# Sheet2_Power_Supply.net
KiCad netlist of a schematic drawn in Altium Designer
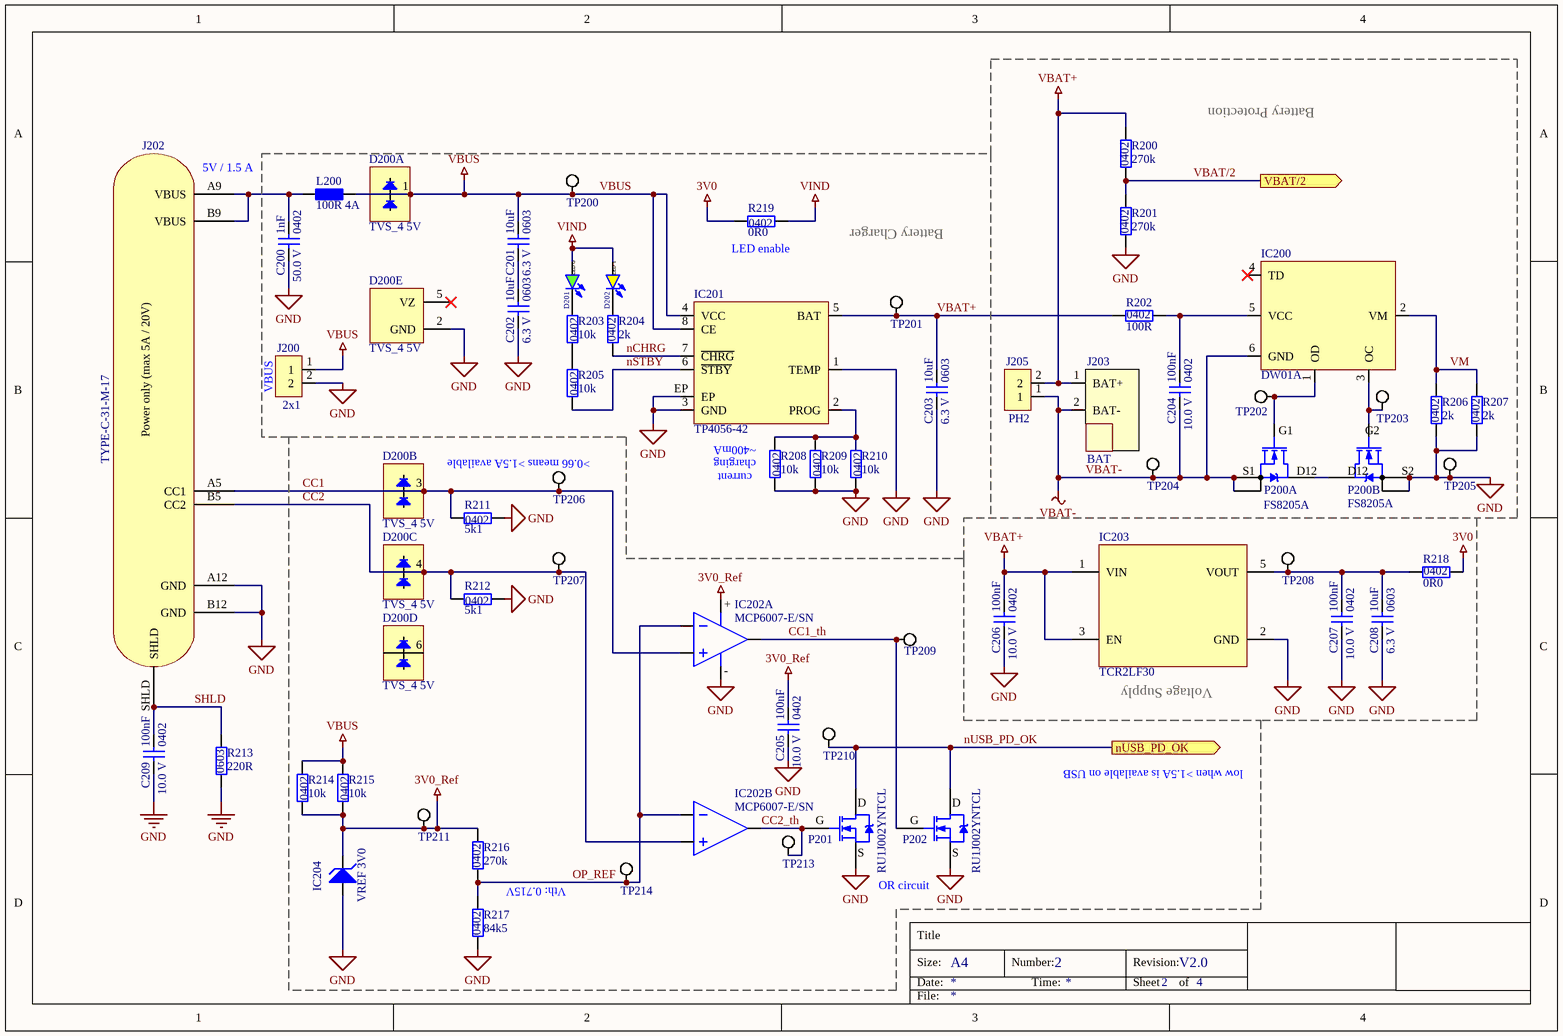
[diagram p0: Sheet2_Power_Supply.SchDoc]

(export (version "E")
  (design (tool "Eeschema 10.0.6"))
  (components
    (comp (ref "C200")
      (value "C 1nF 0402 50V")
      (footprint "0402")
      (description "CAP CER 1000PF 50V C0G/NP0 0402")
      (fields
        (field (name "MANUFACTURER") "Murata Electronics")
        (field (name "MANUFACTURER PART NUMBER") "GRM1555C1H102JA01J")
        (field (name "CAPACITANCE") "1nF")
        (field (name "VOLTAGE") "50.0 V")
      )
      (libsource (lib "CS_Part_Library") (part "CAP_1nF_50V_0402"))
    )
    (comp (ref "C201")
      (value "C 10uF 0603 6.3V")
      (footprint "0603")
      (description "CAP CER 10UF 6.3V X5R 0603")
      (fields
        (field (name "MANUFACTURER") "Taiyo Yuden")
        (field (name "MANUFACTURER PART NUMBER") "JMK107ABJ106MA-T")
        (field (name "CAPACITANCE") "10uF")
        (field (name "VOLTAGE") "6.3 V")
      )
      (libsource (lib "CS_Part_Library") (part "CAP_10uF_6V3_0603"))
    )
    (comp (ref "C202")
      (value "C 10uF 0603 6.3V")
      (footprint "0603")
      (description "CAP CER 10UF 6.3V X5R 0603")
      (fields
        (field (name "MANUFACTURER") "Taiyo Yuden")
        (field (name "MANUFACTURER PART NUMBER") "JMK107ABJ106MA-T")
        (field (name "CAPACITANCE") "10uF")
        (field (name "VOLTAGE") "6.3 V")
      )
      (libsource (lib "CS_Part_Library") (part "CAP_10uF_6V3_0603"))
    )
    (comp (ref "C203")
      (value "C 10uF 0603 6.3V")
      (footprint "0603")
      (description "CAP CER 10UF 6.3V X5R 0603")
      (fields
        (field (name "MANUFACTURER") "Taiyo Yuden")
        (field (name "MANUFACTURER PART NUMBER") "JMK107ABJ106MA-T")
        (field (name "CAPACITANCE") "10uF")
        (field (name "VOLTAGE") "6.3 V")
      )
      (libsource (lib "CS_Part_Library") (part "CAP_10uF_6V3_0603"))
    )
    (comp (ref "C204")
      (value "C 100nF 0402 10V")
      (footprint "0402")
      (description "CAP CER 0.1UF 10V X5R 0402")
      (fields
        (field (name "MANUFACTURER") "Samsung Electro-Mechanics")
        (field (name "MANUFACTURER PART NUMBER") "CL05A104MP5NNNC")
        (field (name "CAPACITANCE") "100nF")
        (field (name "VOLTAGE") "10.0 V")
      )
      (libsource (lib "CS_Part_Library") (part "CAP_100nF_10V_0402"))
    )
    (comp (ref "C205")
      (value "C 100nF 0402 10V")
      (footprint "0402")
      (description "CAP CER 0.1UF 10V X5R 0402")
      (fields
        (field (name "MANUFACTURER") "Samsung Electro-Mechanics")
        (field (name "MANUFACTURER PART NUMBER") "CL05A104MP5NNNC")
        (field (name "CAPACITANCE") "100nF")
        (field (name "VOLTAGE") "10.0 V")
      )
      (libsource (lib "CS_Part_Library") (part "CAP_100nF_10V_0402"))
    )
    (comp (ref "C206")
      (value "C 100nF 0402 10V")
      (footprint "0402")
      (description "CAP CER 0.1UF 10V X5R 0402")
      (fields
        (field (name "MANUFACTURER") "Samsung Electro-Mechanics")
        (field (name "MANUFACTURER PART NUMBER") "CL05A104MP5NNNC")
        (field (name "CAPACITANCE") "100nF")
        (field (name "VOLTAGE") "10.0 V")
      )
      (libsource (lib "CS_Part_Library") (part "CAP_100nF_10V_0402"))
    )
    (comp (ref "C207")
      (value "C 100nF 0402 10V")
      (footprint "0402")
      (description "CAP CER 0.1UF 10V X5R 0402")
      (fields
        (field (name "MANUFACTURER") "Samsung Electro-Mechanics")
        (field (name "MANUFACTURER PART NUMBER") "CL05A104MP5NNNC")
        (field (name "CAPACITANCE") "100nF")
        (field (name "VOLTAGE") "10.0 V")
      )
      (libsource (lib "CS_Part_Library") (part "CAP_100nF_10V_0402"))
    )
    (comp (ref "C208")
      (value "C 10uF 0603 6.3V")
      (footprint "0603")
      (description "CAP CER 10UF 6.3V X5R 0603")
      (fields
        (field (name "MANUFACTURER") "Taiyo Yuden")
        (field (name "MANUFACTURER PART NUMBER") "JMK107ABJ106MA-T")
        (field (name "CAPACITANCE") "10uF")
        (field (name "VOLTAGE") "6.3 V")
      )
      (libsource (lib "CS_Part_Library") (part "CAP_10uF_6V3_0603"))
    )
    (comp (ref "C209")
      (value "C 100nF 0402 10V")
      (footprint "0402")
      (description "CAP CER 0.1UF 10V X5R 0402")
      (fields
        (field (name "MANUFACTURER") "Samsung Electro-Mechanics")
        (field (name "MANUFACTURER PART NUMBER") "CL05A104MP5NNNC")
        (field (name "CAPACITANCE") "100nF")
        (field (name "VOLTAGE") "10.0 V")
      )
      (libsource (lib "CS_Part_Library") (part "CAP_100nF_10V_0402"))
    )
    (comp (ref "D200")
      (value "TVS_4 5V")
      (footprint "SOT-23-6")
      (description "TVS DIODE 5VWM 12.5VC SOT23-6")
      (fields
        (field (name "MANUFACTURER") "Comchip Technology")
        (field (name "MANUFACTURER PART NUMBER") "CPDT6-5V0UPC-HF")
      )
      (libsource (lib "CS_Part_Library") (part "D_TVS_U4_12V5"))
    )
    (comp (ref "D201")
      (value "LED G")
      (footprint "LED_0603")
      (description "LED GREEN DIFFUSED 0603 SMD")
      (fields
        (field (name "MANUFACTURER") "OSRAM Opto Semiconductors Inc.")
        (field (name "MANUFACTURER PART NUMBER") "LT Q39G-Q1OO-25-1")
      )
      (libsource (lib "CS_Part_Library") (part "D_LED_Green_0603"))
    )
    (comp (ref "D202")
      (value "LED Y")
      (footprint "LED_0603")
      (description "LED YELLOW DIFFUSED")
      (fields
        (field (name "MANUFACTURER") "Stanley Electric Co")
        (field (name "MANUFACTURER PART NUMBER") "FKY1111C-TR")
      )
      (libsource (lib "CS_Part_Library") (part "D_LED_Yellow_0603"))
    )
    (comp (ref "IC200")
      (value "DW01A")
      (footprint "SOT-23-6")
      (description "IC BATT MANAGEMENT SOT-23-6")
      (fields (field (name "MANUFACTURER") "PUOLOP"))
      (libsource (lib "Symbols") (part "IC_BAT_PROT_DW01A"))
    )
    (comp (ref "IC201")
      (value "TP4056-42")
      (footprint "SOIC-8-EP")
      (description "IC BATT CHG LI-ION 1CELL ESOP-8-EP")
      (fields
        (field (name "MANUFACTURER") "TOPPOWER(Nanjing Extension Microelectronics)")
        (field (name "MANUFACTURER PART NUMBER") "TP4056-42-ESOP8")
      )
      (libsource (lib "Symbols") (part "IC_BAT_CHGR_TP4056"))
    )
    (comp (ref "IC202")
      (value "MCP6007-E/SN")
      (footprint "SOIC-8")
      (description "DUAL, 1MHZ OP AMP, E TEMP")
      (fields (field (name "MANUFACTURER") "Microchip Technology"))
      (libsource (lib "CS_Part_Library") (part "IC_OpAmp_MCP6007-E/SN"))
    )
    (comp (ref "IC203")
      (value "TCR2LF30")
      (footprint "SOT-23-5")
      (description "IC REG LINEAR 3V 200MA SMV")
      (fields
        (field (name "MANUFACTURER") "Toshiba Semiconductor and Storage")
        (field (name "MANUFACTURER PART NUMBER") "TCR2LF30,LM(CT")
      )
      (libsource (lib "CS_Part_Library") (part "IC_Reg_TCR2LF30"))
    )
    (comp (ref "IC204")
      (value "VREF 3V0")
      (footprint "SOT-23-3")
      (description "IC VREF SHUNT 1% SOT23-3")
      (fields
        (field (name "MANUFACTURER") "Texas Instruments")
        (field (name "MANUFACTURER PART NUMBER") "LM4040DIM3X-3.0/NOPB")
      )
      (libsource (lib "Symbols") (part "IC_Ref_LM4040DIM3X-3.0"))
    )
    (comp (ref "J200")
      (value "2x1")
      (footprint "PH_1x2")
      (description "CONN HEADER VERT 2POS 2.54MM")
      (fields
        (field (name "MANUFACTURER") "Sullins Connector Solutions")
        (field (name "MANUFACTURER PART NUMBER") "PRPC002SAAN-RC")
      )
      (libsource (lib "CS_Part_Library") (part "J_MH2x1_2.54"))
    )
    (comp (ref "J202")
      (value "TYPE-C-31-M-17")
      (footprint "Con_TYPE-C-31-M-17")
      (description "USB4 GEN3, TYPE C, TOP MOUNT")
      (fields (field (name "MANUFACTURER") "Korean Hroparts Elec"))
      (libsource (lib "Symbols") (part "J_USB-C_2"))
    )
    (comp (ref "J203")
      (value "BAT")
      (footprint "J_BAT_CLIP_18650")
      (description "SMT Battery Connectors 18650")
      (fields (field (name "MANUFACTURER") "MYOUNG") (field (name "MANUFACTURER PART NUMBER") "MY-18650-02"))
      (libsource (lib "Symbols") (part "J_BAT_CLIP_18650_A"))
    )
    (comp (ref "J204")
      (value "BAT")
      (description "SMT Battery Connectors 18650")
      (fields (field (name "MANUFACTURER") "MYOUNG") (field (name "MANUFACTURER PART NUMBER") "MY-18650-02"))
      (libsource (lib "Symbols") (part "J_BAT_CLIP_18650_B"))
    )
    (comp (ref "J205")
      (value "PH2")
      (footprint "J_S2B-PH-K-S")
      (description "CONN HEADER R/A 2POS 2MM")
      (fields
        (field (name "MANUFACTURER") "JST Sales America Inc.")
        (field (name "MANUFACTURER PART NUMBER") "S2B-PH-KL(LF)(SN)")
      )
      (libsource (lib "Symbols") (part "J_S2B-PH-KL"))
    )
    (comp (ref "L200")
      (value "L Ferrite 100R 4A")
      (footprint "L_1206")
      (description "FIXED IND 100 4000MA 1206")
      (fields
        (field (name "MANUFACTURER") "Eaton - Electronics Division")
        (field (name "MANUFACTURER PART NUMBER") "MFBM1V3216-101-R")
        (field (name "INDUCTANCE") "100R 4A")
      )
      (libsource (lib "CS_Part_Library") (part "L_100R_4A"))
    )
    (comp (ref "P200")
      (value "P2 NMOS 20V 6A")
      (footprint "TSSOP-8_4.4mm")
      (description "MOSFET 2N_CH 20V 6A TSSOP-8")
      (fields
        (field (name "MANUFACTURER") "Fortune Semicon")
        (field (name "MANUFACTURER PART NUMBER") "FS8205A")
      )
      (libsource (lib "Symbols") (part "P_2NCH_20V_1W"))
    )
    (comp (ref "P201")
      (value "P_NCH_50V_150mW")
      (footprint "UMT3F")
      (description "MOSFET N-CH 50V 200MA UMT3F")
      (fields
        (field (name "MANUFACTURER") "Rohm Semiconductor")
        (field (name "MANUFACTURER PART NUMBER") "RU1J002YNTCL")
      )
      (libsource (lib "CS_Part_Library") (part "P_NCH_50V_150mW"))
    )
    (comp (ref "P202")
      (value "P_NCH_50V_150mW")
      (footprint "UMT3F")
      (description "MOSFET N-CH 50V 200MA UMT3F")
      (fields
        (field (name "MANUFACTURER") "Rohm Semiconductor")
        (field (name "MANUFACTURER PART NUMBER") "RU1J002YNTCL")
      )
      (libsource (lib "CS_Part_Library") (part "P_NCH_50V_150mW"))
    )
    (comp (ref "R200")
      (value "R 270k 0402")
      (footprint "0402")
      (description "RES 270K OHM 1% 1/16W 0402")
      (fields
        (field (name "MANUFACTURER") "YAGEO")
        (field (name "MANUFACTURER PART NUMBER") "RC0402FR-07270KL")
        (field (name "RESISTANCE") "270k")
      )
      (libsource (lib "CS_Part_Library") (part "R_270k_0402"))
    )
    (comp (ref "R201")
      (value "R 270k 0402")
      (footprint "0402")
      (description "RES 270K OHM 1% 1/16W 0402")
      (fields
        (field (name "MANUFACTURER") "YAGEO")
        (field (name "MANUFACTURER PART NUMBER") "RC0402FR-07270KL")
        (field (name "RESISTANCE") "270k")
      )
      (libsource (lib "CS_Part_Library") (part "R_270k_0402"))
    )
    (comp (ref "R202")
      (value "R 100R 0402")
      (footprint "0402")
      (description "RES 100 OHM 1% 1/16W 0402")
      (fields
        (field (name "MANUFACTURER") "Stackpole Electronics Inc")
        (field (name "MANUFACTURER PART NUMBER") "RMCF0402FT100R")
        (field (name "RESISTANCE") "100R")
      )
      (libsource (lib "CS_Part_Library") (part "R_100R_0402"))
    )
    (comp (ref "R203")
      (value "R 10k 0402")
      (footprint "0402")
      (description "RES 10K OHM 1% 1/16W 0402")
      (fields
        (field (name "MANUFACTURER") "YAGEO")
        (field (name "MANUFACTURER PART NUMBER") "RC0402FR-0710KL")
        (field (name "RESISTANCE") "10k")
      )
      (libsource (lib "CS_Part_Library") (part "R_10k_0402"))
    )
    (comp (ref "R204")
      (value "R 2k 0402")
      (footprint "0402")
      (description "RES 2K OHM 1% 1/16W 0402")
      (fields
        (field (name "MANUFACTURER") "Stackpole Electronics Inc")
        (field (name "MANUFACTURER PART NUMBER") "RMCF0402FT2K00")
        (field (name "RESISTANCE") "2k")
      )
      (libsource (lib "CS_Part_Library") (part "R_2k_0402"))
    )
    (comp (ref "R205")
      (value "R 10k 0402")
      (footprint "0402")
      (description "RES 10K OHM 1% 1/16W 0402")
      (fields
        (field (name "MANUFACTURER") "YAGEO")
        (field (name "MANUFACTURER PART NUMBER") "RC0402FR-0710KL")
        (field (name "RESISTANCE") "10k")
      )
      (libsource (lib "CS_Part_Library") (part "R_10k_0402"))
    )
    (comp (ref "R206")
      (value "R 2k 0402")
      (footprint "0402")
      (description "RES 2K OHM 1% 1/16W 0402")
      (fields
        (field (name "MANUFACTURER") "Stackpole Electronics Inc")
        (field (name "MANUFACTURER PART NUMBER") "RMCF0402FT2K00")
        (field (name "RESISTANCE") "2k")
      )
      (libsource (lib "CS_Part_Library") (part "R_2k_0402"))
    )
    (comp (ref "R207")
      (value "R 2k 0402")
      (footprint "0402")
      (description "RES 2K OHM 1% 1/16W 0402")
      (fields
        (field (name "MANUFACTURER") "Stackpole Electronics Inc")
        (field (name "MANUFACTURER PART NUMBER") "RMCF0402FT2K00")
        (field (name "RESISTANCE") "2k")
      )
      (libsource (lib "CS_Part_Library") (part "R_2k_0402"))
    )
    (comp (ref "R208")
      (value "R 10k 0402")
      (footprint "0402")
      (description "RES 10K OHM 1% 1/16W 0402")
      (fields
        (field (name "MANUFACTURER") "YAGEO")
        (field (name "MANUFACTURER PART NUMBER") "RC0402FR-0710KL")
        (field (name "RESISTANCE") "10k")
      )
      (libsource (lib "CS_Part_Library") (part "R_10k_0402"))
    )
    (comp (ref "R209")
      (value "R 10k 0402")
      (footprint "0402")
      (description "RES 10K OHM 1% 1/16W 0402")
      (fields
        (field (name "MANUFACTURER") "YAGEO")
        (field (name "MANUFACTURER PART NUMBER") "RC0402FR-0710KL")
        (field (name "RESISTANCE") "10k")
      )
      (libsource (lib "CS_Part_Library") (part "R_10k_0402"))
    )
    (comp (ref "R210")
      (value "R 10k 0402")
      (footprint "0402")
      (description "RES 10K OHM 1% 1/16W 0402")
      (fields
        (field (name "MANUFACTURER") "YAGEO")
        (field (name "MANUFACTURER PART NUMBER") "RC0402FR-0710KL")
        (field (name "RESISTANCE") "10k")
      )
      (libsource (lib "CS_Part_Library") (part "R_10k_0402"))
    )
    (comp (ref "R211")
      (value "R 5k1 0402")
      (footprint "0402")
      (description "RES 5.1K OHM 1% 1/16W 0402")
      (fields
        (field (name "MANUFACTURER") "Stackpole Electronics Inc")
        (field (name "MANUFACTURER PART NUMBER") "RMCF0402FT5K10")
        (field (name "RESISTANCE") "5k1")
      )
      (libsource (lib "CS_Part_Library") (part "R_5k1_0420"))
    )
    (comp (ref "R212")
      (value "R 5k1 0402")
      (footprint "0402")
      (description "RES 5.1K OHM 1% 1/16W 0402")
      (fields
        (field (name "MANUFACTURER") "Stackpole Electronics Inc")
        (field (name "MANUFACTURER PART NUMBER") "RMCF0402FT5K10")
        (field (name "RESISTANCE") "5k1")
      )
      (libsource (lib "CS_Part_Library") (part "R_5k1_0420"))
    )
    (comp (ref "R213")
      (value "R 220R 0603")
      (footprint "0603")
      (description "RES 220 OHM 1% 1/10W 0603")
      (fields
        (field (name "MANUFACTURER") "Stackpole Electronics Inc")
        (field (name "MANUFACTURER PART NUMBER") "RMCF0603FT220R")
        (field (name "RESISTANCE") "220R")
      )
      (libsource (lib "CS_Part_Library") (part "R_220R_0603"))
    )
    (comp (ref "R214")
      (value "R 10k 0402")
      (footprint "0402")
      (description "RES 10K OHM 1% 1/16W 0402")
      (fields
        (field (name "MANUFACTURER") "YAGEO")
        (field (name "MANUFACTURER PART NUMBER") "RC0402FR-0710KL")
        (field (name "RESISTANCE") "10k")
      )
      (libsource (lib "CS_Part_Library") (part "R_10k_0402"))
    )
    (comp (ref "R215")
      (value "R 10k 0402")
      (footprint "0402")
      (description "RES 10K OHM 1% 1/16W 0402")
      (fields
        (field (name "MANUFACTURER") "YAGEO")
        (field (name "MANUFACTURER PART NUMBER") "RC0402FR-0710KL")
        (field (name "RESISTANCE") "10k")
      )
      (libsource (lib "CS_Part_Library") (part "R_10k_0402"))
    )
    (comp (ref "R216")
      (value "R 270k 0402")
      (footprint "0402")
      (description "RES 270K OHM 1% 1/16W 0402")
      (fields
        (field (name "MANUFACTURER") "YAGEO")
        (field (name "MANUFACTURER PART NUMBER") "RC0402FR-07270KL")
        (field (name "RESISTANCE") "270k")
      )
      (libsource (lib "CS_Part_Library") (part "R_270k_0402"))
    )
    (comp (ref "R217")
      (value "R 84k5 0402")
      (footprint "0402")
      (description "RES SMD 84.5K OHM 1% 1/16W 0402")
      (fields
        (field (name "MANUFACTURER") "Vishay Dale")
        (field (name "MANUFACTURER PART NUMBER") "CRCW040284K5FKED")
        (field (name "RESISTANCE") "84k5")
      )
      (libsource (lib "CS_Part_Library") (part "R_84k5_0402"))
    )
    (comp (ref "R218")
      (value "R 0R0 0402")
      (footprint "0402")
      (description "RES 0 OHM JUMPER 1/16W 0402")
      (fields
        (field (name "MANUFACTURER") "Stackpole Electronics Inc")
        (field (name "MANUFACTURER PART NUMBER") "RMCF0402ZT0R00")
        (field (name "RESISTANCE") "0R0")
      )
      (libsource (lib "") (part "R_0R0_0402_1"))
    )
    (comp (ref "R219")
      (value "R 0R0 0402")
      (footprint "0402")
      (description "RES 0 OHM JUMPER 1/16W 0402")
      (fields
        (field (name "MANUFACTURER") "Stackpole Electronics Inc")
        (field (name "MANUFACTURER PART NUMBER") "RMCF0402ZT0R00")
        (field (name "RESISTANCE") "0R0")
      )
      (libsource (lib "CS_Part_Library") (part "R_0R0_0402"))
    )
    (comp (ref "TP200")
      (value "TP")
      (footprint "TP_1mm")
      (description "Test Point 1mm")
      (libsource (lib "CS_Part_Library") (part "TP_1mm"))
    )
    (comp (ref "TP201")
      (value "TP")
      (footprint "TP_1mm")
      (description "Test Point 1mm")
      (libsource (lib "CS_Part_Library") (part "TP_1mm"))
    )
    (comp (ref "TP202")
      (value "TP")
      (footprint "TP_1mm")
      (description "Test Point 1mm")
      (libsource (lib "CS_Part_Library") (part "TP_1mm"))
    )
    (comp (ref "TP203")
      (value "TP")
      (footprint "TP_1mm")
      (description "Test Point 1mm")
      (libsource (lib "CS_Part_Library") (part "TP_1mm"))
    )
    (comp (ref "TP204")
      (value "TP")
      (footprint "TP_1mm")
      (description "Test Point 1mm")
      (libsource (lib "CS_Part_Library") (part "TP_1mm"))
    )
    (comp (ref "TP205")
      (value "TP")
      (footprint "TP_1mm")
      (description "Test Point 1mm")
      (libsource (lib "CS_Part_Library") (part "TP_1mm"))
    )
    (comp (ref "TP206")
      (value "TP")
      (footprint "TP_1mm")
      (description "Test Point 1mm")
      (libsource (lib "CS_Part_Library") (part "TP_1mm"))
    )
    (comp (ref "TP207")
      (value "TP")
      (footprint "TP_1mm")
      (description "Test Point 1mm")
      (libsource (lib "CS_Part_Library") (part "TP_1mm"))
    )
    (comp (ref "TP208")
      (value "TP")
      (footprint "TP_1mm")
      (description "Test Point 1mm")
      (libsource (lib "CS_Part_Library") (part "TP_1mm"))
    )
    (comp (ref "TP209")
      (value "TP")
      (footprint "TP_1mm")
      (description "Test Point 1mm")
      (libsource (lib "CS_Part_Library") (part "TP_1mm"))
    )
    (comp (ref "TP210")
      (value "TP")
      (footprint "TP_1mm")
      (description "Test Point 1mm")
      (libsource (lib "CS_Part_Library") (part "TP_1mm"))
    )
    (comp (ref "TP211")
      (value "TP")
      (footprint "TP_1mm")
      (description "Test Point 1mm")
      (libsource (lib "CS_Part_Library") (part "TP_1mm"))
    )
    (comp (ref "TP213")
      (value "TP")
      (footprint "TP_1mm")
      (description "Test Point 1mm")
      (libsource (lib "CS_Part_Library") (part "TP_1mm"))
    )
    (comp (ref "TP214")
      (value "TP")
      (footprint "TP_1mm")
      (description "Test Point 1mm")
      (libsource (lib "CS_Part_Library") (part "TP_1mm"))
    )
  )
  (nets
    (net (code "1") (name "/CC1") (class "Default")
      (node (ref "D200") (pin "3") (pinfunction "3_3") (pintype "passive"))
      (node (ref "IC202") (pin "3") (pinfunction "INA+_3") (pintype "passive"))
      (node (ref "J202") (pin "A5") (pinfunction "CC1_A5") (pintype "passive"))
      (node (ref "R211") (pin "2") (pinfunction "2_2") (pintype "passive"))
      (node (ref "TP206") (pin "1") (pinfunction "TP_1") (pintype "passive"))
    )
    (net (code "2") (name "/CC1_th") (class "Default")
      (node (ref "IC202") (pin "1") (pinfunction "OUTA_1") (pintype "passive"))
      (node (ref "P202") (pin "1") (pinfunction "G_1") (pintype "passive"))
      (node (ref "TP209") (pin "1") (pinfunction "TP_1") (pintype "passive"))
    )
    (net (code "3") (name "/CC2") (class "Default")
      (node (ref "D200") (pin "4") (pinfunction "4_4") (pintype "passive"))
      (node (ref "IC202") (pin "5") (pinfunction "INB+_5") (pintype "passive"))
      (node (ref "J202") (pin "B5") (pinfunction "CC2_B5") (pintype "passive"))
      (node (ref "R212") (pin "2") (pinfunction "2_2") (pintype "passive"))
      (node (ref "TP207") (pin "1") (pinfunction "TP_1") (pintype "passive"))
    )
    (net (code "4") (name "/CC2_th") (class "Default")
      (node (ref "IC202") (pin "7") (pinfunction "OUTB_7") (pintype "passive"))
      (node (ref "P201") (pin "1") (pinfunction "G_1") (pintype "passive"))
      (node (ref "TP213") (pin "1") (pinfunction "TP_1") (pintype "passive"))
    )
    (net (code "5") (name "/OP_REF") (class "Default")
      (node (ref "IC202") (pin "2") (pinfunction "INA-_2") (pintype "passive"))
      (node (ref "IC202") (pin "6") (pinfunction "INB-_6") (pintype "passive"))
      (node (ref "R216") (pin "1") (pinfunction "1_1") (pintype "passive"))
      (node (ref "R217") (pin "2") (pinfunction "2_2") (pintype "passive"))
      (node (ref "TP214") (pin "1") (pinfunction "TP_1") (pintype "passive"))
    )
    (net (code "6") (name "/SHLD") (class "Default")
      (node (ref "C209") (pin "2") (pinfunction "2_2") (pintype "passive"))
      (node (ref "J202") (pin "SHLD") (pinfunction "SHLD_SHLD") (pintype "passive"))
      (node (ref "R213") (pin "2") (pinfunction "2_2") (pintype "passive"))
    )
    (net (code "7") (name "/VBAT{slash}2") (class "Default")
      (node (ref "R200") (pin "1") (pinfunction "1_1") (pintype "passive"))
      (node (ref "R201") (pin "2") (pinfunction "2_2") (pintype "passive"))
    )
    (net (code "8") (name "/VM") (class "Default")
      (node (ref "IC200") (pin "2") (pinfunction "VM_2") (pintype "passive"))
      (node (ref "R206") (pin "2") (pinfunction "2_2") (pintype "passive"))
      (node (ref "R207") (pin "2") (pinfunction "2_2") (pintype "passive"))
    )
    (net (code "9") (name "/nCHRG") (class "Default")
      (node (ref "IC201") (pin "7") (pinfunction "~{CHRG}_7") (pintype "passive"))
      (node (ref "R204") (pin "1") (pinfunction "1_1") (pintype "passive"))
    )
    (net (code "10") (name "/nSTBY") (class "Default")
      (node (ref "IC201") (pin "6") (pinfunction "~{STBY}_6") (pintype "passive"))
      (node (ref "R205") (pin "1") (pinfunction "1_1") (pintype "passive"))
    )
    (net (code "11") (name "/nUSB_PD_OK") (class "Default")
      (node (ref "P201") (pin "3") (pinfunction "D_3") (pintype "passive"))
      (node (ref "P202") (pin "3") (pinfunction "D_3") (pintype "passive"))
      (node (ref "TP210") (pin "1") (pinfunction "TP_1") (pintype "passive"))
    )
    (net (code "12") (name "3V0") (class "Default")
      (node (ref "R218") (pin "2") (pinfunction "2_2") (pintype "passive"))
      (node (ref "R219") (pin "2") (pinfunction "2_2") (pintype "passive"))
    )
    (net (code "13") (name "3V0_Ref") (class "Default")
      (node (ref "C205") (pin "2") (pinfunction "2_2") (pintype "passive"))
      (node (ref "IC202") (pin "8") (pinfunction "VDD_8") (pintype "passive"))
      (node (ref "IC204") (pin "1") (pinfunction "K_1") (pintype "passive"))
      (node (ref "R214") (pin "1") (pinfunction "1_1") (pintype "passive"))
      (node (ref "R215") (pin "1") (pinfunction "1_1") (pintype "passive"))
      (node (ref "R216") (pin "2") (pinfunction "2_2") (pintype "passive"))
      (node (ref "TP211") (pin "1") (pinfunction "TP_1") (pintype "passive"))
    )
    (net (code "14") (name "GND") (class "Default")
      (node (ref "C200") (pin "1") (pinfunction "1_1") (pintype "passive"))
      (node (ref "C202") (pin "1") (pinfunction "1_1") (pintype "passive"))
      (node (ref "C203") (pin "1") (pinfunction "1_1") (pintype "passive"))
      (node (ref "C205") (pin "1") (pinfunction "1_1") (pintype "passive"))
      (node (ref "C206") (pin "1") (pinfunction "1_1") (pintype "passive"))
      (node (ref "C207") (pin "1") (pinfunction "1_1") (pintype "passive"))
      (node (ref "C208") (pin "1") (pinfunction "1_1") (pintype "passive"))
      (node (ref "C209") (pin "1") (pinfunction "1_1") (pintype "passive"))
      (node (ref "D200") (pin "2") (pinfunction "GND_2") (pintype "passive"))
      (node (ref "IC201") (pin "1") (pinfunction "TEMP_1") (pintype "passive"))
      (node (ref "IC201") (pin "3") (pinfunction "GND_3") (pintype "passive"))
      (node (ref "IC201") (pin "EP") (pinfunction "EP_EP") (pintype "passive"))
      (node (ref "IC202") (pin "4") (pinfunction "VSS_4") (pintype "passive"))
      (node (ref "IC203") (pin "2") (pinfunction "GND_2") (pintype "passive"))
      (node (ref "IC204") (pin "2") (pinfunction "A_2") (pintype "passive"))
      (node (ref "J200") (pin "2") (pinfunction "2_2") (pintype "passive"))
      (node (ref "J202") (pin "A12") (pinfunction "GND_A12") (pintype "passive"))
      (node (ref "J202") (pin "B12") (pinfunction "GND_B12") (pintype "passive"))
      (node (ref "P200") (pin "6") (pinfunction "S2_6") (pintype "passive"))
      (node (ref "P200") (pin "7") (pinfunction "S2_7") (pintype "passive"))
      (node (ref "P201") (pin "2") (pinfunction "S_2") (pintype "passive"))
      (node (ref "P202") (pin "2") (pinfunction "S_2") (pintype "passive"))
      (node (ref "R201") (pin "1") (pinfunction "1_1") (pintype "passive"))
      (node (ref "R206") (pin "1") (pinfunction "1_1") (pintype "passive"))
      (node (ref "R207") (pin "1") (pinfunction "1_1") (pintype "passive"))
      (node (ref "R208") (pin "1") (pinfunction "1_1") (pintype "passive"))
      (node (ref "R209") (pin "1") (pinfunction "1_1") (pintype "passive"))
      (node (ref "R210") (pin "1") (pinfunction "1_1") (pintype "passive"))
      (node (ref "R211") (pin "1") (pinfunction "1_1") (pintype "passive"))
      (node (ref "R212") (pin "1") (pinfunction "1_1") (pintype "passive"))
      (node (ref "R213") (pin "1") (pinfunction "1_1") (pintype "passive"))
      (node (ref "R217") (pin "1") (pinfunction "1_1") (pintype "passive"))
      (node (ref "TP205") (pin "1") (pinfunction "TP_1") (pintype "passive"))
    )
    (net (code "15") (name "Net-(C200-Pad2)") (class "Default")
      (node (ref "C200") (pin "2") (pinfunction "2_2") (pintype "passive"))
      (node (ref "J202") (pin "A9") (pinfunction "VBUS_A9") (pintype "passive"))
      (node (ref "J202") (pin "B9") (pinfunction "VBUS_B9") (pintype "passive"))
      (node (ref "L200") (pin "1") (pinfunction "1_1") (pintype "passive"))
    )
    (net (code "16") (name "Net-(C201-Pad1)") (class "Default")
      (node (ref "C201") (pin "1") (pinfunction "1_1") (pintype "passive"))
      (node (ref "C202") (pin "2") (pinfunction "2_2") (pintype "passive"))
    )
    (net (code "17") (name "Net-(D201-PadK)") (class "Default")
      (node (ref "D201") (pin "K") (pinfunction "K_K") (pintype "passive"))
      (node (ref "R203") (pin "2") (pinfunction "2_2") (pintype "passive"))
    )
    (net (code "18") (name "Net-(D202-PadK)") (class "Default")
      (node (ref "D202") (pin "K") (pinfunction "K_K") (pintype "passive"))
      (node (ref "R204") (pin "2") (pinfunction "2_2") (pintype "passive"))
    )
    (net (code "19") (name "Net-(IC200-OC)") (class "Default")
      (node (ref "IC200") (pin "3") (pinfunction "OC_3") (pintype "passive"))
      (node (ref "P200") (pin "5") (pinfunction "G1_5") (pintype "passive"))
      (node (ref "TP203") (pin "1") (pinfunction "TP_1") (pintype "passive"))
    )
    (net (code "20") (name "Net-(IC200-OD)") (class "Default")
      (node (ref "IC200") (pin "1") (pinfunction "OD_1") (pintype "passive"))
      (node (ref "P200") (pin "4") (pinfunction "G1_4") (pintype "passive"))
      (node (ref "TP202") (pin "1") (pinfunction "TP_1") (pintype "passive"))
    )
    (net (code "21") (name "Net-(IC200-VCC)") (class "Default")
      (node (ref "C204") (pin "2") (pinfunction "2_2") (pintype "passive"))
      (node (ref "IC200") (pin "5") (pinfunction "VCC_5") (pintype "passive"))
      (node (ref "R202") (pin "2") (pinfunction "2_2") (pintype "passive"))
    )
    (net (code "22") (name "Net-(IC201-PROG)") (class "Default")
      (node (ref "IC201") (pin "2") (pinfunction "PROG_2") (pintype "passive"))
      (node (ref "R208") (pin "2") (pinfunction "2_2") (pintype "passive"))
      (node (ref "R209") (pin "2") (pinfunction "2_2") (pintype "passive"))
      (node (ref "R210") (pin "2") (pinfunction "2_2") (pintype "passive"))
    )
    (net (code "23") (name "Net-(IC203-VOUT)") (class "Default")
      (node (ref "C207") (pin "2") (pinfunction "2_2") (pintype "passive"))
      (node (ref "C208") (pin "2") (pinfunction "2_2") (pintype "passive"))
      (node (ref "IC203") (pin "5") (pinfunction "VOUT_5") (pintype "passive"))
      (node (ref "R218") (pin "1") (pinfunction "1_1") (pintype "passive"))
      (node (ref "TP208") (pin "1") (pinfunction "TP_1") (pintype "passive"))
    )
    (net (code "24") (name "Net-(P200A-D12)") (class "Default")
      (node (ref "P200") (pin "1") (pinfunction "D12_1") (pintype "passive"))
      (node (ref "P200") (pin "8") (pinfunction "D12_8") (pintype "passive"))
    )
    (net (code "25") (name "Net-(R203-Pad1)") (class "Default")
      (node (ref "R203") (pin "1") (pinfunction "1_1") (pintype "passive"))
      (node (ref "R205") (pin "2") (pinfunction "2_2") (pintype "passive"))
    )
    (net (code "26") (name "VBAT+") (class "Default")
      (node (ref "C203") (pin "2") (pinfunction "2_2") (pintype "passive"))
      (node (ref "C206") (pin "2") (pinfunction "2_2") (pintype "passive"))
      (node (ref "IC201") (pin "5") (pinfunction "BAT_5") (pintype "passive"))
      (node (ref "IC203") (pin "1") (pinfunction "VIN_1") (pintype "passive"))
      (node (ref "IC203") (pin "3") (pinfunction "EN_3") (pintype "passive"))
      (node (ref "J203") (pin "1") (pinfunction "BAT+_1") (pintype "passive"))
      (node (ref "J205") (pin "2") (pinfunction "2_2") (pintype "passive"))
      (node (ref "R200") (pin "2") (pinfunction "2_2") (pintype "passive"))
      (node (ref "R202") (pin "1") (pinfunction "1_1") (pintype "passive"))
      (node (ref "TP201") (pin "1") (pinfunction "TP_1") (pintype "passive"))
    )
    (net (code "27") (name "VBAT-") (class "Default")
      (node (ref "C204") (pin "1") (pinfunction "1_1") (pintype "passive"))
      (node (ref "IC200") (pin "6") (pinfunction "GND_6") (pintype "passive"))
      (node (ref "J203") (pin "2") (pinfunction "BAT-_2") (pintype "passive"))
      (node (ref "J205") (pin "1") (pinfunction "1_1") (pintype "passive"))
      (node (ref "P200") (pin "2") (pinfunction "S1_2") (pintype "passive"))
      (node (ref "P200") (pin "3") (pinfunction "S1_3") (pintype "passive"))
      (node (ref "TP204") (pin "1") (pinfunction "TP_1") (pintype "passive"))
    )
    (net (code "28") (name "VBUS") (class "Default")
      (node (ref "C201") (pin "2") (pinfunction "2_2") (pintype "passive"))
      (node (ref "D200") (pin "1") (pinfunction "1_1") (pintype "passive"))
      (node (ref "IC201") (pin "4") (pinfunction "VCC_4") (pintype "passive"))
      (node (ref "IC201") (pin "8") (pinfunction "CE_8") (pintype "passive"))
      (node (ref "J200") (pin "1") (pinfunction "1_1") (pintype "passive"))
      (node (ref "L200") (pin "2") (pinfunction "2_2") (pintype "passive"))
      (node (ref "R214") (pin "2") (pinfunction "2_2") (pintype "passive"))
      (node (ref "R215") (pin "2") (pinfunction "2_2") (pintype "passive"))
      (node (ref "TP200") (pin "1") (pinfunction "TP_1") (pintype "passive"))
    )
    (net (code "29") (name "VIND") (class "Default")
      (node (ref "D201") (pin "A") (pinfunction "A_A") (pintype "passive"))
      (node (ref "D202") (pin "A") (pinfunction "A_A") (pintype "passive"))
      (node (ref "R219") (pin "1") (pinfunction "1_1") (pintype "passive"))
    )
    (net (code "30") (name "unconnected-(D200-Pad6)") (class "Default")
      (node (ref "D200") (pin "6") (pinfunction "6_6") (pintype "passive"))
    )
    (net (code "31") (name "unconnected-(D200E-VZ-Pad5)") (class "Default")
      (node (ref "D200") (pin "5") (pinfunction "VZ_5") (pintype "passive+no_connect"))
    )
    (net (code "32") (name "unconnected-(IC200-TD-Pad4)") (class "Default")
      (node (ref "IC200") (pin "4") (pinfunction "TD_4") (pintype "passive+no_connect"))
    )
  )
)
